# Sheet1.net
KiCad netlist of a schematic drawn in Altium Designer
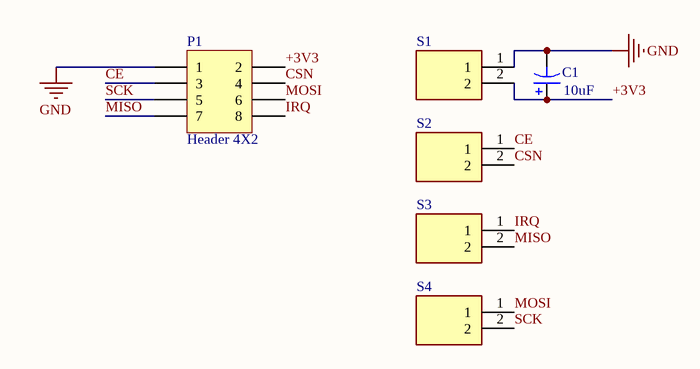
[diagram p0: Sheet1.SchDoc]

(export (version "E")
  (design (tool "Eeschema 10.0.6"))
  (components
    (comp (ref "C1")
      (value "10uF")
      (footprint "RB7.6-15")
      (description "Polarized Capacitor (Radial)")
      (fields (field (name "Comment") "Cap") (field (name "PUBLISHER") "Altium Limited"))
      (libsource (lib "Miscellaneous Devices") (part "Cap Pol1"))
    )
    (comp (ref "P1")
      (value "Header 4X2")
      (footprint "HDR2X4")
      (description "Header, 4-Pin, Dual row")
      (fields (field (name "PUBLISHER") "Altium Limited"))
      (libsource (lib "Miscellaneous Connectors") (part "Header 4X2"))
    )
    (comp (ref "S1")
      (value "~")
      (footprint "SamacSys:TB00250002BE")
      (description "Connector")
      (fields
        (field (name "MANUFACTURER_PART_NUMBER") "TB002-500-02BE")
        (field (name "MOUSER PART NUMBER") "490-TB002-500-02BE")
      )
      (libsource (lib "*") (part "TB002-500-02BE"))
    )
    (comp (ref "S2")
      (value "~")
      (footprint "SamacSys:TB00250002BE")
      (description "Connector")
      (fields
        (field (name "MANUFACTURER_PART_NUMBER") "TB002-500-02BE")
        (field (name "MOUSER PART NUMBER") "490-TB002-500-02BE")
      )
      (libsource (lib "*") (part "TB002-500-02BE"))
    )
    (comp (ref "S3")
      (value "~")
      (footprint "SamacSys:TB00250002BE")
      (description "Connector")
      (fields
        (field (name "MANUFACTURER_PART_NUMBER") "TB002-500-02BE")
        (field (name "MOUSER PART NUMBER") "490-TB002-500-02BE")
      )
      (libsource (lib "*") (part "TB002-500-02BE"))
    )
    (comp (ref "S4")
      (value "~")
      (footprint "SamacSys:TB00250002BE")
      (description "Connector")
      (fields
        (field (name "MANUFACTURER_PART_NUMBER") "TB002-500-02BE")
        (field (name "MOUSER PART NUMBER") "490-TB002-500-02BE")
      )
      (libsource (lib "*") (part "TB002-500-02BE"))
    )
  )
  (nets
    (net (code "1") (name "/+3V3") (class "Default")
      (node (ref "C1") (pin "1") (pinfunction "1_1") (pintype "passive"))
      (node (ref "P1") (pin "2") (pinfunction "2_2") (pintype "passive"))
      (node (ref "S1") (pin "2") (pinfunction "2_2") (pintype "passive"))
    )
    (net (code "2") (name "/CE") (class "Default")
      (node (ref "P1") (pin "3") (pinfunction "3_3") (pintype "passive"))
      (node (ref "S2") (pin "1") (pinfunction "1_1") (pintype "passive"))
    )
    (net (code "3") (name "/CSN") (class "Default")
      (node (ref "P1") (pin "4") (pinfunction "4_4") (pintype "passive"))
      (node (ref "S2") (pin "2") (pinfunction "2_2") (pintype "passive"))
    )
    (net (code "4") (name "/IRQ") (class "Default")
      (node (ref "P1") (pin "8") (pinfunction "8_8") (pintype "passive"))
      (node (ref "S3") (pin "1") (pinfunction "1_1") (pintype "passive"))
    )
    (net (code "5") (name "/MISO") (class "Default")
      (node (ref "P1") (pin "7") (pinfunction "7_7") (pintype "passive"))
      (node (ref "S3") (pin "2") (pinfunction "2_2") (pintype "passive"))
    )
    (net (code "6") (name "/MOSI") (class "Default")
      (node (ref "P1") (pin "6") (pinfunction "6_6") (pintype "passive"))
      (node (ref "S4") (pin "1") (pinfunction "1_1") (pintype "passive"))
    )
    (net (code "7") (name "/SCK") (class "Default")
      (node (ref "P1") (pin "5") (pinfunction "5_5") (pintype "passive"))
      (node (ref "S4") (pin "2") (pinfunction "2_2") (pintype "passive"))
    )
    (net (code "8") (name "GND") (class "Default")
      (node (ref "C1") (pin "2") (pinfunction "2_2") (pintype "passive"))
      (node (ref "P1") (pin "1") (pinfunction "1_1") (pintype "passive"))
      (node (ref "S1") (pin "1") (pinfunction "1_1") (pintype "passive"))
    )
  )
)
